# RoverWing-cover-V5.net
KiCad netlist of a schematic drawn in EAGLE
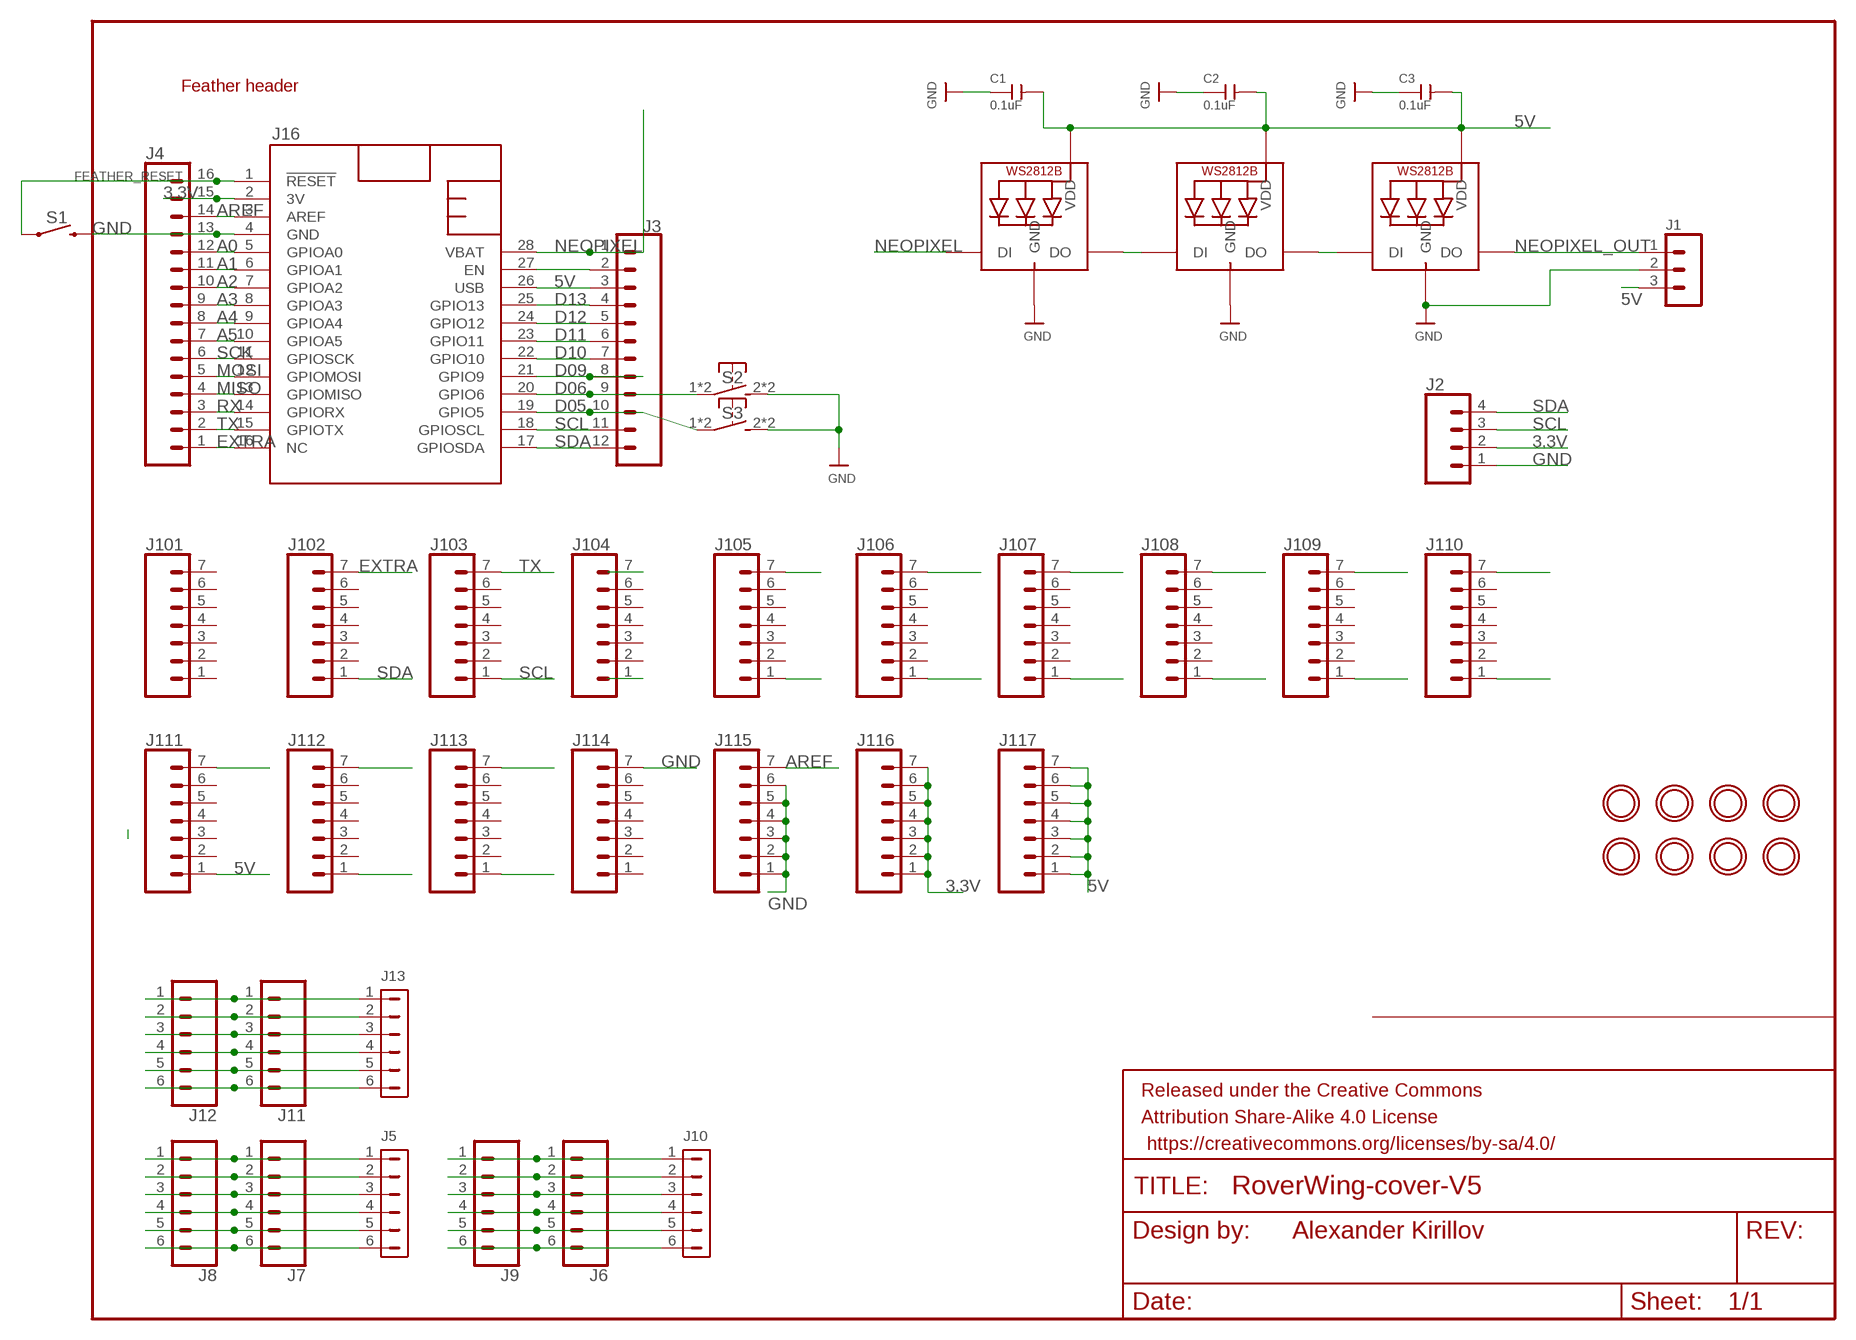
[diagram p0: schematic, sheet 1]

(export (version "E")
  (design (tool "Eeschema 10.0.6"))
  (components
    (comp (ref "C1")
      (value "0.1uF")
      (footprint "eagle-import:C0805")
      (libsource (lib "eagle-import") (part "CAP-CERAMIC-SMD-0805"))
    )
    (comp (ref "C2")
      (value "0.1uF")
      (footprint "eagle-import:C0805")
      (libsource (lib "eagle-import") (part "CAP-CERAMIC-SMD-0805"))
    )
    (comp (ref "C3")
      (value "0.1uF")
      (footprint "eagle-import:C0805")
      (libsource (lib "eagle-import") (part "CAP-CERAMIC-SMD-0805"))
    )
    (comp (ref "FRAME2")
      (value "FRAME-LETTERNO_PACKAGE")
      (footprint "eagle-import:DUMMY")
      (fields (field (name "DESIGNER") "Nobody"))
      (libsource (lib "eagle-import") (part "FRAME-LETTERNO_PACKAGE"))
    )
    (comp (ref "J1")
      (value "HEADER-PH-3PSIDEENTRY")
      (footprint "eagle-import:S3B-PH-K")
      (fields (field (name "PARTNO") "S3B-PH-K-S(LF)(SN)"))
      (libsource (lib "eagle-import") (part "HEADER-PH-3PSIDEENTRY"))
    )
    (comp (ref "J2")
      (value "CONN_04")
      (footprint "eagle-import:1X04")
      (libsource (lib "eagle-import") (part "CONN_04"))
    )
    (comp (ref "J3")
      (value "CONN_12NO_SILK")
      (footprint "eagle-import:1X12_NO_SILK")
      (libsource (lib "eagle-import") (part "CONN_12NO_SILK"))
    )
    (comp (ref "J4")
      (value "CONN_161X16_NO_SILK")
      (footprint "eagle-import:1X16_NO_SILK")
      (libsource (lib "eagle-import") (part "CONN_161X16_NO_SILK"))
    )
    (comp (ref "J5")
      (value "HEADER-PH-6PSIDEENTRY")
      (footprint "eagle-import:S6B-PH-K")
      (libsource (lib "eagle-import") (part "HEADER-PH-6PSIDEENTRY"))
    )
    (comp (ref "J6")
      (value "CONN_06NO_SILK_NO_POP")
      (footprint "eagle-import:1X06_NO_SILK")
      (libsource (lib "eagle-import") (part "CONN_06NO_SILK_NO_POP"))
    )
    (comp (ref "J7")
      (value "CONN_06NO_SILK_NO_POP")
      (footprint "eagle-import:1X06_NO_SILK")
      (libsource (lib "eagle-import") (part "CONN_06NO_SILK_NO_POP"))
    )
    (comp (ref "J8")
      (value "CONN_06NO_SILK_NO_POP")
      (footprint "eagle-import:1X06_NO_SILK")
      (libsource (lib "eagle-import") (part "CONN_06NO_SILK_NO_POP"))
    )
    (comp (ref "J9")
      (value "CONN_06NO_SILK_NO_POP")
      (footprint "eagle-import:1X06_NO_SILK")
      (libsource (lib "eagle-import") (part "CONN_06NO_SILK_NO_POP"))
    )
    (comp (ref "J10")
      (value "HEADER-PH-6PSIDEENTRY")
      (footprint "eagle-import:S6B-PH-K")
      (libsource (lib "eagle-import") (part "HEADER-PH-6PSIDEENTRY"))
    )
    (comp (ref "J11")
      (value "CONN_06NO_SILK_NO_POP")
      (footprint "eagle-import:1X06_NO_SILK")
      (libsource (lib "eagle-import") (part "CONN_06NO_SILK_NO_POP"))
    )
    (comp (ref "J12")
      (value "CONN_06NO_SILK_NO_POP")
      (footprint "eagle-import:1X06_NO_SILK")
      (libsource (lib "eagle-import") (part "CONN_06NO_SILK_NO_POP"))
    )
    (comp (ref "J13")
      (value "HEADER-PH-6PSIDEENTRY")
      (footprint "eagle-import:S6B-PH-K")
      (libsource (lib "eagle-import") (part "HEADER-PH-6PSIDEENTRY"))
    )
    (comp (ref "J16")
      (value "FEATHERWING_NODIM")
      (footprint "eagle-import:FEATHERWING_DIM")
      (libsource (lib "eagle-import") (part "FEATHERWING_NODIM"))
    )
    (comp (ref "J101")
      (value "CONN_07NO_SILK")
      (footprint "eagle-import:1X07_NO_SILK")
      (libsource (lib "eagle-import") (part "CONN_07NO_SILK"))
    )
    (comp (ref "J102")
      (value "CONN_07NO_SILK")
      (footprint "eagle-import:1X07_NO_SILK")
      (libsource (lib "eagle-import") (part "CONN_07NO_SILK"))
    )
    (comp (ref "J103")
      (value "CONN_07NO_SILK")
      (footprint "eagle-import:1X07_NO_SILK")
      (libsource (lib "eagle-import") (part "CONN_07NO_SILK"))
    )
    (comp (ref "J104")
      (value "CONN_07NO_SILK")
      (footprint "eagle-import:1X07_NO_SILK")
      (libsource (lib "eagle-import") (part "CONN_07NO_SILK"))
    )
    (comp (ref "J105")
      (value "CONN_07NO_SILK")
      (footprint "eagle-import:1X07_NO_SILK")
      (libsource (lib "eagle-import") (part "CONN_07NO_SILK"))
    )
    (comp (ref "J106")
      (value "CONN_07NO_SILK")
      (footprint "eagle-import:1X07_NO_SILK")
      (libsource (lib "eagle-import") (part "CONN_07NO_SILK"))
    )
    (comp (ref "J107")
      (value "CONN_07NO_SILK")
      (footprint "eagle-import:1X07_NO_SILK")
      (libsource (lib "eagle-import") (part "CONN_07NO_SILK"))
    )
    (comp (ref "J108")
      (value "CONN_07NO_SILK")
      (footprint "eagle-import:1X07_NO_SILK")
      (libsource (lib "eagle-import") (part "CONN_07NO_SILK"))
    )
    (comp (ref "J109")
      (value "CONN_07NO_SILK")
      (footprint "eagle-import:1X07_NO_SILK")
      (libsource (lib "eagle-import") (part "CONN_07NO_SILK"))
    )
    (comp (ref "J110")
      (value "CONN_07NO_SILK")
      (footprint "eagle-import:1X07_NO_SILK")
      (libsource (lib "eagle-import") (part "CONN_07NO_SILK"))
    )
    (comp (ref "J111")
      (value "CONN_07NO_SILK")
      (footprint "eagle-import:1X07_NO_SILK")
      (libsource (lib "eagle-import") (part "CONN_07NO_SILK"))
    )
    (comp (ref "J112")
      (value "CONN_07NO_SILK")
      (footprint "eagle-import:1X07_NO_SILK")
      (libsource (lib "eagle-import") (part "CONN_07NO_SILK"))
    )
    (comp (ref "J113")
      (value "CONN_07NO_SILK")
      (footprint "eagle-import:1X07_NO_SILK")
      (libsource (lib "eagle-import") (part "CONN_07NO_SILK"))
    )
    (comp (ref "J114")
      (value "CONN_07NO_SILK")
      (footprint "eagle-import:1X07_NO_SILK")
      (libsource (lib "eagle-import") (part "CONN_07NO_SILK"))
    )
    (comp (ref "J115")
      (value "CONN_07NO_SILK")
      (footprint "eagle-import:1X07_NO_SILK")
      (libsource (lib "eagle-import") (part "CONN_07NO_SILK"))
    )
    (comp (ref "J116")
      (value "CONN_07NO_SILK")
      (footprint "eagle-import:1X07_NO_SILK")
      (libsource (lib "eagle-import") (part "CONN_07NO_SILK"))
    )
    (comp (ref "J117")
      (value "CONN_07NO_SILK")
      (footprint "eagle-import:1X07_NO_SILK")
      (libsource (lib "eagle-import") (part "CONN_07NO_SILK"))
    )
    (comp (ref "LED1")
      (value "WS2812B5050")
      (footprint "eagle-import:WS2812B")
      (libsource (lib "eagle-import") (part "WS2812B5050"))
    )
    (comp (ref "LED2")
      (value "WS2812B5050")
      (footprint "eagle-import:WS2812B")
      (libsource (lib "eagle-import") (part "WS2812B5050"))
    )
    (comp (ref "LED3")
      (value "WS2812B5050")
      (footprint "eagle-import:WS2812B")
      (libsource (lib "eagle-import") (part "WS2812B5050"))
    )
    (comp (ref "S1")
      (value "MOMENTARY-SWITCH-SPST-PTH-6.0MM")
      (footprint "eagle-import:TACTILE_SWITCH_PTH_6.0MM")
      (libsource (lib "eagle-import") (part "MOMENTARY-SWITCH-SPST-PTH-6.0MM"))
    )
    (comp (ref "S2")
      (value "SW-TACTILE-4.5X4.5_SMD")
      (footprint "eagle-import:TL3305")
      (libsource (lib "eagle-import") (part "SW-TACTILE-4.5X4.5_SMD"))
    )
    (comp (ref "S3")
      (value "SW-TACTILE-4.5X4.5_SMD")
      (footprint "eagle-import:TL3305")
      (libsource (lib "eagle-import") (part "SW-TACTILE-4.5X4.5_SMD"))
    )
    (comp (ref "U$3")
      (value "MOUNTINGHOLE3.0_NPH")
      (footprint "eagle-import:MOUNTINGHOLE_3.0_NPH")
      (libsource (lib "eagle-import") (part "MOUNTINGHOLE3.0_NPH"))
    )
    (comp (ref "U$4")
      (value "MOUNTINGHOLE3.0_NPH")
      (footprint "eagle-import:MOUNTINGHOLE_3.0_NPH")
      (libsource (lib "eagle-import") (part "MOUNTINGHOLE3.0_NPH"))
    )
    (comp (ref "U$14")
      (value "MOUNTINGHOLE3.0_NPH")
      (footprint "eagle-import:MOUNTINGHOLE_3.0_NPH")
      (libsource (lib "eagle-import") (part "MOUNTINGHOLE3.0_NPH"))
    )
    (comp (ref "U$15")
      (value "MOUNTINGHOLE3.0_NPH")
      (footprint "eagle-import:MOUNTINGHOLE_3.0_NPH")
      (libsource (lib "eagle-import") (part "MOUNTINGHOLE3.0_NPH"))
    )
    (comp (ref "U$24")
      (value "MOUNTINGHOLE3.0_NPH")
      (footprint "eagle-import:MOUNTINGHOLE_3.0_NPH")
      (libsource (lib "eagle-import") (part "MOUNTINGHOLE3.0_NPH"))
    )
    (comp (ref "U$25")
      (value "MOUNTINGHOLE3.0_NPH")
      (footprint "eagle-import:MOUNTINGHOLE_3.0_NPH")
      (libsource (lib "eagle-import") (part "MOUNTINGHOLE3.0_NPH"))
    )
    (comp (ref "U$26")
      (value "MOUNTINGHOLE3.0_NPH")
      (footprint "eagle-import:MOUNTINGHOLE_3.0_NPH")
      (libsource (lib "eagle-import") (part "MOUNTINGHOLE3.0_NPH"))
    )
    (comp (ref "U$27")
      (value "MOUNTINGHOLE3.0_NPH")
      (footprint "eagle-import:MOUNTINGHOLE_3.0_NPH")
      (libsource (lib "eagle-import") (part "MOUNTINGHOLE3.0_NPH"))
    )
  )
  (nets
    (net (code "1") (name "/3.3V") (class "Default")
      (node (ref "J116") (pin "1") (pinfunction "1_1") (pintype "passive"))
      (node (ref "J116") (pin "2") (pinfunction "2_2") (pintype "passive"))
      (node (ref "J116") (pin "3") (pinfunction "3_3") (pintype "passive"))
      (node (ref "J116") (pin "4") (pinfunction "4_4") (pintype "passive"))
      (node (ref "J116") (pin "5") (pinfunction "5_5") (pintype "passive"))
      (node (ref "J116") (pin "6") (pinfunction "6_6") (pintype "passive"))
      (node (ref "J116") (pin "7") (pinfunction "7_7") (pintype "passive"))
      (node (ref "J16") (pin "2") (pinfunction "3V_2") (pintype "power_in"))
      (node (ref "J2") (pin "2") (pinfunction "2_2") (pintype "passive"))
      (node (ref "J4") (pin "15") (pinfunction "15_15") (pintype "passive"))
    )
    (net (code "2") (name "/5V") (class "Default")
      (node (ref "C1") (pin "2") (pinfunction "2_2") (pintype "passive"))
      (node (ref "C2") (pin "2") (pinfunction "2_2") (pintype "passive"))
      (node (ref "C3") (pin "2") (pinfunction "2_2") (pintype "passive"))
      (node (ref "J1") (pin "3") (pinfunction "3_3") (pintype "passive"))
      (node (ref "J111") (pin "1") (pinfunction "1_1") (pintype "passive"))
      (node (ref "J117") (pin "1") (pinfunction "1_1") (pintype "passive"))
      (node (ref "J117") (pin "2") (pinfunction "2_2") (pintype "passive"))
      (node (ref "J117") (pin "3") (pinfunction "3_3") (pintype "passive"))
      (node (ref "J117") (pin "4") (pinfunction "4_4") (pintype "passive"))
      (node (ref "J117") (pin "5") (pinfunction "5_5") (pintype "passive"))
      (node (ref "J117") (pin "6") (pinfunction "6_6") (pintype "passive"))
      (node (ref "J117") (pin "7") (pinfunction "7_7") (pintype "passive"))
      (node (ref "J16") (pin "26") (pinfunction "USB_26") (pintype "power_in"))
      (node (ref "J3") (pin "3") (pinfunction "3_3") (pintype "passive"))
      (node (ref "LED1") (pin "1-VDD") (pinfunction "VDD_1-VDD") (pintype "power_in"))
      (node (ref "LED2") (pin "1-VDD") (pinfunction "VDD_1-VDD") (pintype "power_in"))
      (node (ref "LED3") (pin "1-VDD") (pinfunction "VDD_1-VDD") (pintype "power_in"))
    )
    (net (code "3") (name "/A0") (class "Default")
      (node (ref "J113") (pin "7") (pinfunction "7_7") (pintype "passive"))
      (node (ref "J16") (pin "5") (pinfunction "GPIOA0_5") (pintype "bidirectional"))
      (node (ref "J4") (pin "12") (pinfunction "12_12") (pintype "passive"))
    )
    (net (code "4") (name "/A1") (class "Default")
      (node (ref "J112") (pin "7") (pinfunction "7_7") (pintype "passive"))
      (node (ref "J16") (pin "6") (pinfunction "GPIOA1_6") (pintype "bidirectional"))
      (node (ref "J4") (pin "11") (pinfunction "11_11") (pintype "passive"))
    )
    (net (code "5") (name "/A2") (class "Default")
      (node (ref "J111") (pin "7") (pinfunction "7_7") (pintype "passive"))
      (node (ref "J16") (pin "7") (pinfunction "GPIOA2_7") (pintype "bidirectional"))
      (node (ref "J4") (pin "10") (pinfunction "10_10") (pintype "passive"))
    )
    (net (code "6") (name "/A3") (class "Default")
      (node (ref "J110") (pin "7") (pinfunction "7_7") (pintype "passive"))
      (node (ref "J16") (pin "8") (pinfunction "GPIOA3_8") (pintype "bidirectional"))
      (node (ref "J4") (pin "9") (pinfunction "9_9") (pintype "passive"))
    )
    (net (code "7") (name "/A4") (class "Default")
      (node (ref "J109") (pin "7") (pinfunction "7_7") (pintype "passive"))
      (node (ref "J16") (pin "9") (pinfunction "GPIOA4_9") (pintype "bidirectional"))
      (node (ref "J4") (pin "8") (pinfunction "8_8") (pintype "passive"))
    )
    (net (code "8") (name "/A5") (class "Default")
      (node (ref "J108") (pin "7") (pinfunction "7_7") (pintype "passive"))
      (node (ref "J16") (pin "10") (pinfunction "GPIOA5_10") (pintype "bidirectional"))
      (node (ref "J4") (pin "7") (pinfunction "7_7") (pintype "passive"))
    )
    (net (code "9") (name "/AREF") (class "Default")
      (node (ref "J115") (pin "7") (pinfunction "7_7") (pintype "passive"))
      (node (ref "J16") (pin "3") (pinfunction "AREF_3") (pintype "passive"))
      (node (ref "J4") (pin "14") (pinfunction "14_14") (pintype "passive"))
    )
    (net (code "10") (name "/D05") (class "Default")
      (node (ref "J104") (pin "1") (pinfunction "1_1") (pintype "passive"))
      (node (ref "J16") (pin "19") (pinfunction "GPIO5_19") (pintype "bidirectional"))
      (node (ref "J3") (pin "10") (pinfunction "10_10") (pintype "passive"))
      (node (ref "S3") (pin "1") (pinfunction "P1_1") (pintype "passive"))
      (node (ref "S3") (pin "4") (pinfunction "P1_4") (pintype "passive"))
    )
    (net (code "11") (name "/D06") (class "Default")
      (node (ref "J105") (pin "1") (pinfunction "1_1") (pintype "passive"))
      (node (ref "J16") (pin "20") (pinfunction "GPIO6_20") (pintype "bidirectional"))
      (node (ref "J3") (pin "9") (pinfunction "9_9") (pintype "passive"))
      (node (ref "S2") (pin "1") (pinfunction "P1_1") (pintype "passive"))
      (node (ref "S2") (pin "4") (pinfunction "P1_4") (pintype "passive"))
    )
    (net (code "12") (name "/D09") (class "Default")
      (node (ref "J106") (pin "1") (pinfunction "1_1") (pintype "passive"))
      (node (ref "J16") (pin "21") (pinfunction "GPIO9_21") (pintype "bidirectional"))
      (node (ref "J3") (pin "8") (pinfunction "8_8") (pintype "passive"))
    )
    (net (code "13") (name "/D10") (class "Default")
      (node (ref "J107") (pin "1") (pinfunction "1_1") (pintype "passive"))
      (node (ref "J16") (pin "22") (pinfunction "GPIO10_22") (pintype "bidirectional"))
      (node (ref "J3") (pin "7") (pinfunction "7_7") (pintype "passive"))
    )
    (net (code "14") (name "/D11") (class "Default")
      (node (ref "J108") (pin "1") (pinfunction "1_1") (pintype "passive"))
      (node (ref "J16") (pin "23") (pinfunction "GPIO11_23") (pintype "bidirectional"))
      (node (ref "J3") (pin "6") (pinfunction "6_6") (pintype "passive"))
    )
    (net (code "15") (name "/D12") (class "Default")
      (node (ref "J109") (pin "1") (pinfunction "1_1") (pintype "passive"))
      (node (ref "J16") (pin "24") (pinfunction "GPIO12_24") (pintype "bidirectional"))
      (node (ref "J3") (pin "5") (pinfunction "5_5") (pintype "passive"))
    )
    (net (code "16") (name "/D13") (class "Default")
      (node (ref "J110") (pin "1") (pinfunction "1_1") (pintype "passive"))
      (node (ref "J16") (pin "25") (pinfunction "GPIO13_25") (pintype "bidirectional"))
      (node (ref "J3") (pin "4") (pinfunction "4_4") (pintype "passive"))
    )
    (net (code "17") (name "/EXTRA") (class "Default")
      (node (ref "J102") (pin "7") (pinfunction "7_7") (pintype "passive"))
      (node (ref "J16") (pin "16") (pinfunction "NC_16") (pintype "passive"))
      (node (ref "J4") (pin "1") (pinfunction "1_1") (pintype "passive"))
    )
    (net (code "18") (name "/FEATHER_RESET") (class "Default")
      (node (ref "J16") (pin "1") (pinfunction "~{RESET}_1") (pintype "input"))
      (node (ref "J4") (pin "16") (pinfunction "16_16") (pintype "passive"))
      (node (ref "S1") (pin "1") (pinfunction "1_1") (pintype "passive"))
    )
    (net (code "19") (name "/MISO") (class "Default")
      (node (ref "J105") (pin "7") (pinfunction "7_7") (pintype "passive"))
      (node (ref "J16") (pin "13") (pinfunction "GPIOMISO_13") (pintype "bidirectional"))
      (node (ref "J4") (pin "4") (pinfunction "4_4") (pintype "passive"))
    )
    (net (code "20") (name "/MOSI") (class "Default")
      (node (ref "J106") (pin "7") (pinfunction "7_7") (pintype "passive"))
      (node (ref "J16") (pin "12") (pinfunction "GPIOMOSI_12") (pintype "bidirectional"))
      (node (ref "J4") (pin "5") (pinfunction "5_5") (pintype "passive"))
    )
    (net (code "21") (name "/N$37") (class "Default")
      (node (ref "J112") (pin "1") (pinfunction "1_1") (pintype "passive"))
      (node (ref "J16") (pin "27") (pinfunction "EN_27") (pintype "passive"))
      (node (ref "J3") (pin "2") (pinfunction "2_2") (pintype "passive"))
    )
    (net (code "22") (name "/NEOPIXEL") (class "Default")
      (node (ref "J16") (pin "28") (pinfunction "VBAT_28") (pintype "power_in"))
      (node (ref "J3") (pin "1") (pinfunction "1_1") (pintype "passive"))
      (node (ref "LED1") (pin "4-DIN") (pinfunction "DI_4-DIN") (pintype "input"))
    )
    (net (code "23") (name "/NEOPIXEL_OUT") (class "Default")
      (node (ref "J1") (pin "1") (pinfunction "1_1") (pintype "passive"))
      (node (ref "LED3") (pin "2-DOUT") (pinfunction "DO_2-DOUT") (pintype "output"))
    )
    (net (code "24") (name "/RX") (class "Default")
      (node (ref "J104") (pin "7") (pinfunction "7_7") (pintype "passive"))
      (node (ref "J16") (pin "14") (pinfunction "GPIORX_14") (pintype "bidirectional"))
      (node (ref "J4") (pin "3") (pinfunction "3_3") (pintype "passive"))
    )
    (net (code "25") (name "/SCK") (class "Default")
      (node (ref "J107") (pin "7") (pinfunction "7_7") (pintype "passive"))
      (node (ref "J16") (pin "11") (pinfunction "GPIOSCK_11") (pintype "bidirectional"))
      (node (ref "J4") (pin "6") (pinfunction "6_6") (pintype "passive"))
    )
    (net (code "26") (name "/SCL") (class "Default")
      (node (ref "J103") (pin "1") (pinfunction "1_1") (pintype "passive"))
      (node (ref "J16") (pin "18") (pinfunction "GPIOSCL_18") (pintype "bidirectional"))
      (node (ref "J2") (pin "3") (pinfunction "3_3") (pintype "passive"))
      (node (ref "J3") (pin "11") (pinfunction "11_11") (pintype "passive"))
    )
    (net (code "27") (name "/SDA") (class "Default")
      (node (ref "J102") (pin "1") (pinfunction "1_1") (pintype "passive"))
      (node (ref "J16") (pin "17") (pinfunction "GPIOSDA_17") (pintype "bidirectional"))
      (node (ref "J2") (pin "4") (pinfunction "4_4") (pintype "passive"))
      (node (ref "J3") (pin "12") (pinfunction "12_12") (pintype "passive"))
    )
    (net (code "28") (name "/TX") (class "Default")
      (node (ref "J103") (pin "7") (pinfunction "7_7") (pintype "passive"))
      (node (ref "J16") (pin "15") (pinfunction "GPIOTX_15") (pintype "bidirectional"))
      (node (ref "J4") (pin "2") (pinfunction "2_2") (pintype "passive"))
    )
    (net (code "29") (name "GND") (class "Default")
      (node (ref "C1") (pin "1") (pinfunction "1_1") (pintype "passive"))
      (node (ref "C2") (pin "1") (pinfunction "1_1") (pintype "passive"))
      (node (ref "C3") (pin "1") (pinfunction "1_1") (pintype "passive"))
      (node (ref "J1") (pin "2") (pinfunction "2_2") (pintype "passive"))
      (node (ref "J114") (pin "7") (pinfunction "7_7") (pintype "passive"))
      (node (ref "J115") (pin "1") (pinfunction "1_1") (pintype "passive"))
      (node (ref "J115") (pin "2") (pinfunction "2_2") (pintype "passive"))
      (node (ref "J115") (pin "3") (pinfunction "3_3") (pintype "passive"))
      (node (ref "J115") (pin "4") (pinfunction "4_4") (pintype "passive"))
      (node (ref "J115") (pin "5") (pinfunction "5_5") (pintype "passive"))
      (node (ref "J115") (pin "6") (pinfunction "6_6") (pintype "passive"))
      (node (ref "J16") (pin "4") (pinfunction "GND_4") (pintype "power_in"))
      (node (ref "J2") (pin "1") (pinfunction "1_1") (pintype "passive"))
      (node (ref "J4") (pin "13") (pinfunction "13_13") (pintype "passive"))
      (node (ref "LED1") (pin "3-GND") (pinfunction "GND_3-GND") (pintype "power_in"))
      (node (ref "LED2") (pin "3-GND") (pinfunction "GND_3-GND") (pintype "power_in"))
      (node (ref "LED3") (pin "3-GND") (pinfunction "GND_3-GND") (pintype "power_in"))
      (node (ref "S1") (pin "3") (pinfunction "2_3") (pintype "passive"))
      (node (ref "S2") (pin "2") (pinfunction "S1_2") (pintype "passive"))
      (node (ref "S2") (pin "3") (pinfunction "S1_3") (pintype "passive"))
      (node (ref "S3") (pin "2") (pinfunction "S1_2") (pintype "passive"))
      (node (ref "S3") (pin "3") (pinfunction "S1_3") (pintype "passive"))
    )
    (net (code "30") (name "Net-(J5-Pad1)") (class "Default")
      (node (ref "J5") (pin "1") (pinfunction "1_1") (pintype "passive"))
      (node (ref "J7") (pin "1") (pinfunction "1_1") (pintype "passive"))
      (node (ref "J8") (pin "1") (pinfunction "1_1") (pintype "passive"))
    )
    (net (code "31") (name "Net-(J5-Pad2)") (class "Default")
      (node (ref "J5") (pin "2") (pinfunction "2_2") (pintype "passive"))
      (node (ref "J7") (pin "2") (pinfunction "2_2") (pintype "passive"))
      (node (ref "J8") (pin "2") (pinfunction "2_2") (pintype "passive"))
    )
    (net (code "32") (name "Net-(J5-Pad3)") (class "Default")
      (node (ref "J5") (pin "3") (pinfunction "3_3") (pintype "passive"))
      (node (ref "J7") (pin "3") (pinfunction "3_3") (pintype "passive"))
      (node (ref "J8") (pin "3") (pinfunction "3_3") (pintype "passive"))
    )
    (net (code "33") (name "Net-(J5-Pad4)") (class "Default")
      (node (ref "J5") (pin "4") (pinfunction "4_4") (pintype "passive"))
      (node (ref "J7") (pin "4") (pinfunction "4_4") (pintype "passive"))
      (node (ref "J8") (pin "4") (pinfunction "4_4") (pintype "passive"))
    )
    (net (code "34") (name "Net-(J5-Pad5)") (class "Default")
      (node (ref "J5") (pin "5") (pinfunction "5_5") (pintype "passive"))
      (node (ref "J7") (pin "5") (pinfunction "5_5") (pintype "passive"))
      (node (ref "J8") (pin "5") (pinfunction "5_5") (pintype "passive"))
    )
    (net (code "35") (name "Net-(J5-Pad6)") (class "Default")
      (node (ref "J5") (pin "6") (pinfunction "6_6") (pintype "passive"))
      (node (ref "J7") (pin "6") (pinfunction "6_6") (pintype "passive"))
      (node (ref "J8") (pin "6") (pinfunction "6_6") (pintype "passive"))
    )
    (net (code "36") (name "Net-(J10-Pad1)") (class "Default")
      (node (ref "J10") (pin "1") (pinfunction "1_1") (pintype "passive"))
      (node (ref "J6") (pin "1") (pinfunction "1_1") (pintype "passive"))
      (node (ref "J9") (pin "1") (pinfunction "1_1") (pintype "passive"))
    )
    (net (code "37") (name "Net-(J10-Pad2)") (class "Default")
      (node (ref "J10") (pin "2") (pinfunction "2_2") (pintype "passive"))
      (node (ref "J6") (pin "2") (pinfunction "2_2") (pintype "passive"))
      (node (ref "J9") (pin "2") (pinfunction "2_2") (pintype "passive"))
    )
    (net (code "38") (name "Net-(J10-Pad3)") (class "Default")
      (node (ref "J10") (pin "3") (pinfunction "3_3") (pintype "passive"))
      (node (ref "J6") (pin "3") (pinfunction "3_3") (pintype "passive"))
      (node (ref "J9") (pin "3") (pinfunction "3_3") (pintype "passive"))
    )
    (net (code "39") (name "Net-(J10-Pad4)") (class "Default")
      (node (ref "J10") (pin "4") (pinfunction "4_4") (pintype "passive"))
      (node (ref "J6") (pin "4") (pinfunction "4_4") (pintype "passive"))
      (node (ref "J9") (pin "4") (pinfunction "4_4") (pintype "passive"))
    )
    (net (code "40") (name "Net-(J10-Pad5)") (class "Default")
      (node (ref "J10") (pin "5") (pinfunction "5_5") (pintype "passive"))
      (node (ref "J6") (pin "5") (pinfunction "5_5") (pintype "passive"))
      (node (ref "J9") (pin "5") (pinfunction "5_5") (pintype "passive"))
    )
    (net (code "41") (name "Net-(J10-Pad6)") (class "Default")
      (node (ref "J10") (pin "6") (pinfunction "6_6") (pintype "passive"))
      (node (ref "J6") (pin "6") (pinfunction "6_6") (pintype "passive"))
      (node (ref "J9") (pin "6") (pinfunction "6_6") (pintype "passive"))
    )
    (net (code "42") (name "Net-(J11-Pad1)") (class "Default")
      (node (ref "J11") (pin "1") (pinfunction "1_1") (pintype "passive"))
      (node (ref "J12") (pin "1") (pinfunction "1_1") (pintype "passive"))
      (node (ref "J13") (pin "1") (pinfunction "1_1") (pintype "passive"))
    )
    (net (code "43") (name "Net-(J11-Pad2)") (class "Default")
      (node (ref "J11") (pin "2") (pinfunction "2_2") (pintype "passive"))
      (node (ref "J12") (pin "2") (pinfunction "2_2") (pintype "passive"))
      (node (ref "J13") (pin "2") (pinfunction "2_2") (pintype "passive"))
    )
    (net (code "44") (name "Net-(J11-Pad3)") (class "Default")
      (node (ref "J11") (pin "3") (pinfunction "3_3") (pintype "passive"))
      (node (ref "J12") (pin "3") (pinfunction "3_3") (pintype "passive"))
      (node (ref "J13") (pin "3") (pinfunction "3_3") (pintype "passive"))
    )
    (net (code "45") (name "Net-(J11-Pad4)") (class "Default")
      (node (ref "J11") (pin "4") (pinfunction "4_4") (pintype "passive"))
      (node (ref "J12") (pin "4") (pinfunction "4_4") (pintype "passive"))
      (node (ref "J13") (pin "4") (pinfunction "4_4") (pintype "passive"))
    )
    (net (code "46") (name "Net-(J11-Pad5)") (class "Default")
      (node (ref "J11") (pin "5") (pinfunction "5_5") (pintype "passive"))
      (node (ref "J12") (pin "5") (pinfunction "5_5") (pintype "passive"))
      (node (ref "J13") (pin "5") (pinfunction "5_5") (pintype "passive"))
    )
    (net (code "47") (name "Net-(J11-Pad6)") (class "Default")
      (node (ref "J11") (pin "6") (pinfunction "6_6") (pintype "passive"))
      (node (ref "J12") (pin "6") (pinfunction "6_6") (pintype "passive"))
      (node (ref "J13") (pin "6") (pinfunction "6_6") (pintype "passive"))
    )
    (net (code "48") (name "Net-(LED1-DO)") (class "Default")
      (node (ref "LED1") (pin "2-DOUT") (pinfunction "DO_2-DOUT") (pintype "output"))
      (node (ref "LED2") (pin "4-DIN") (pinfunction "DI_4-DIN") (pintype "input"))
    )
    (net (code "49") (name "Net-(LED2-DO)") (class "Default")
      (node (ref "LED2") (pin "2-DOUT") (pinfunction "DO_2-DOUT") (pintype "output"))
      (node (ref "LED3") (pin "4-DIN") (pinfunction "DI_4-DIN") (pintype "input"))
    )
    (net (code "50") (name "unconnected-(J101-Pad1)") (class "Default")
      (node (ref "J101") (pin "1") (pinfunction "1_1") (pintype "passive"))
    )
    (net (code "51") (name "unconnected-(J101-Pad2)") (class "Default")
      (node (ref "J101") (pin "2") (pinfunction "2_2") (pintype "passive"))
    )
    (net (code "52") (name "unconnected-(J101-Pad3)") (class "Default")
      (node (ref "J101") (pin "3") (pinfunction "3_3") (pintype "passive"))
    )
    (net (code "53") (name "unconnected-(J101-Pad4)") (class "Default")
      (node (ref "J101") (pin "4") (pinfunction "4_4") (pintype "passive"))
    )
    (net (code "54") (name "unconnected-(J101-Pad5)") (class "Default")
      (node (ref "J101") (pin "5") (pinfunction "5_5") (pintype "passive"))
    )
    (net (code "55") (name "unconnected-(J101-Pad6)") (class "Default")
      (node (ref "J101") (pin "6") (pinfunction "6_6") (pintype "passive"))
    )
    (net (code "56") (name "unconnected-(J101-Pad7)") (class "Default")
      (node (ref "J101") (pin "7") (pinfunction "7_7") (pintype "passive"))
    )
    (net (code "57") (name "unconnected-(J102-Pad2)") (class "Default")
      (node (ref "J102") (pin "2") (pinfunction "2_2") (pintype "passive"))
    )
    (net (code "58") (name "unconnected-(J102-Pad3)") (class "Default")
      (node (ref "J102") (pin "3") (pinfunction "3_3") (pintype "passive"))
    )
    (net (code "59") (name "unconnected-(J102-Pad4)") (class "Default")
      (node (ref "J102") (pin "4") (pinfunction "4_4") (pintype "passive"))
    )
    (net (code "60") (name "unconnected-(J102-Pad5)") (class "Default")
      (node (ref "J102") (pin "5") (pinfunction "5_5") (pintype "passive"))
    )
    (net (code "61") (name "unconnected-(J102-Pad6)") (class "Default")
      (node (ref "J102") (pin "6") (pinfunction "6_6") (pintype "passive"))
    )
    (net (code "62") (name "unconnected-(J103-Pad2)") (class "Default")
      (node (ref "J103") (pin "2") (pinfunction "2_2") (pintype "passive"))
    )
    (net (code "63") (name "unconnected-(J103-Pad3)") (class "Default")
      (node (ref "J103") (pin "3") (pinfunction "3_3") (pintype "passive"))
    )
    (net (code "64") (name "unconnected-(J103-Pad4)") (class "Default")
      (node (ref "J103") (pin "4") (pinfunction "4_4") (pintype "passive"))
    )
    (net (code "65") (name "unconnected-(J103-Pad5)") (class "Default")
      (node (ref "J103") (pin "5") (pinfunction "5_5") (pintype "passive"))
    )
    (net (code "66") (name "unconnected-(J103-Pad6)") (class "Default")
      (node (ref "J103") (pin "6") (pinfunction "6_6") (pintype "passive"))
    )
    (net (code "67") (name "unconnected-(J104-Pad2)") (class "Default")
      (node (ref "J104") (pin "2") (pinfunction "2_2") (pintype "passive"))
    )
    (net (code "68") (name "unconnected-(J104-Pad3)") (class "Default")
      (node (ref "J104") (pin "3") (pinfunction "3_3") (pintype "passive"))
    )
    (net (code "69") (name "unconnected-(J104-Pad4)") (class "Default")
      (node (ref "J104") (pin "4") (pinfunction "4_4") (pintype "passive"))
    )
    (net (code "70") (name "unconnected-(J104-Pad5)") (class "Default")
      (node (ref "J104") (pin "5") (pinfunction "5_5") (pintype "passive"))
    )
    (net (code "71") (name "unconnected-(J104-Pad6)") (class "Default")
      (node (ref "J104") (pin "6") (pinfunction "6_6") (pintype "passive"))
    )
    (net (code "72") (name "unconnected-(J105-Pad2)") (class "Default")
      (node (ref "J105") (pin "2") (pinfunction "2_2") (pintype "passive"))
    )
    (net (code "73") (name "unconnected-(J105-Pad3)") (class "Default")
      (node (ref "J105") (pin "3") (pinfunction "3_3") (pintype "passive"))
    )
    (net (code "74") (name "unconnected-(J105-Pad4)") (class "Default")
      (node (ref "J105") (pin "4") (pinfunction "4_4") (pintype "passive"))
    )
    (net (code "75") (name "unconnected-(J105-Pad5)") (class "Default")
      (node (ref "J105") (pin "5") (pinfunction "5_5") (pintype "passive"))
    )
    (net (code "76") (name "unconnected-(J105-Pad6)") (class "Default")
      (node (ref "J105") (pin "6") (pinfunction "6_6") (pintype "passive"))
    )
    (net (code "77") (name "unconnected-(J106-Pad2)") (class "Default")
      (node (ref "J106") (pin "2") (pinfunction "2_2") (pintype "passive"))
    )
    (net (code "78") (name "unconnected-(J106-Pad3)") (class "Default")
      (node (ref "J106") (pin "3") (pinfunction "3_3") (pintype "passive"))
    )
    (net (code "79") (name "unconnected-(J106-Pad4)") (class "Default")
      (node (ref "J106") (pin "4") (pinfunction "4_4") (pintype "passive"))
    )
    (net (code "80") (name "unconnected-(J106-Pad5)") (class "Default")
      (node (ref "J106") (pin "5") (pinfunction "5_5") (pintype "passive"))
    )
    (net (code "81") (name "unconnected-(J106-Pad6)") (class "Default")
      (node (ref "J106") (pin "6") (pinfunction "6_6") (pintype "passive"))
    )
    (net (code "82") (name "unconnected-(J107-Pad2)") (class "Default")
      (node (ref "J107") (pin "2") (pinfunction "2_2") (pintype "passive"))
    )
    (net (code "83") (name "unconnected-(J107-Pad3)") (class "Default")
      (node (ref "J107") (pin "3") (pinfunction "3_3") (pintype "passive"))
    )
    (net (code "84") (name "unconnected-(J107-Pad4)") (class "Default")
      (node (ref "J107") (pin "4") (pinfunction "4_4") (pintype "passive"))
    )
    (net (code "85") (name "unconnected-(J107-Pad5)") (class "Default")
      (node (ref "J107") (pin "5") (pinfunction "5_5") (pintype "passive"))
    )
    (net (code "86") (name "unconnected-(J107-Pad6)") (class "Default")
      (node (ref "J107") (pin "6") (pinfunction "6_6") (pintype "passive"))
    )
    (net (code "87") (name "unconnected-(J108-Pad2)") (class "Default")
      (node (ref "J108") (pin "2") (pinfunction "2_2") (pintype "passive"))
    )
    (net (code "88") (name "unconnected-(J108-Pad3)") (class "Default")
      (node (ref "J108") (pin "3") (pinfunction "3_3") (pintype "passive"))
    )
    (net (code "89") (name "unconnected-(J108-Pad4)") (class "Default")
      (node (ref "J108") (pin "4") (pinfunction "4_4") (pintype "passive"))
    )
    (net (code "90") (name "unconnected-(J108-Pad5)") (class "Default")
      (node (ref "J108") (pin "5") (pinfunction "5_5") (pintype "passive"))
    )
    (net (code "91") (name "unconnected-(J108-Pad6)") (class "Default")
      (node (ref "J108") (pin "6") (pinfunction "6_6") (pintype "passive"))
    )
    (net (code "92") (name "unconnected-(J109-Pad2)") (class "Default")
      (node (ref "J109") (pin "2") (pinfunction "2_2") (pintype "passive"))
    )
    (net (code "93") (name "unconnected-(J109-Pad3)") (class "Default")
      (node (ref "J109") (pin "3") (pinfunction "3_3") (pintype "passive"))
    )
    (net (code "94") (name "unconnected-(J109-Pad4)") (class "Default")
      (node (ref "J109") (pin "4") (pinfunction "4_4") (pintype "passive"))
    )
    (net (code "95") (name "unconnected-(J109-Pad5)") (class "Default")
      (node (ref "J109") (pin "5") (pinfunction "5_5") (pintype "passive"))
    )
    (net (code "96") (name "unconnected-(J109-Pad6)") (class "Default")
      (node (ref "J109") (pin "6") (pinfunction "6_6") (pintype "passive"))
    )
    (net (code "97") (name "unconnected-(J110-Pad2)") (class "Default")
      (node (ref "J110") (pin "2") (pinfunction "2_2") (pintype "passive"))
    )
    (net (code "98") (name "unconnected-(J110-Pad3)") (class "Default")
      (node (ref "J110") (pin "3") (pinfunction "3_3") (pintype "passive"))
    )
    (net (code "99") (name "unconnected-(J110-Pad4)") (class "Default")
      (node (ref "J110") (pin "4") (pinfunction "4_4") (pintype "passive"))
    )
    (net (code "100") (name "unconnected-(J110-Pad5)") (class "Default")
      (node (ref "J110") (pin "5") (pinfunction "5_5") (pintype "passive"))
    )
    (net (code "101") (name "unconnected-(J110-Pad6)") (class "Default")
      (node (ref "J110") (pin "6") (pinfunction "6_6") (pintype "passive"))
    )
    (net (code "102") (name "unconnected-(J111-Pad2)") (class "Default")
      (node (ref "J111") (pin "2") (pinfunction "2_2") (pintype "passive"))
    )
    (net (code "103") (name "unconnected-(J111-Pad3)") (class "Default")
      (node (ref "J111") (pin "3") (pinfunction "3_3") (pintype "passive"))
    )
    (net (code "104") (name "unconnected-(J111-Pad4)") (class "Default")
      (node (ref "J111") (pin "4") (pinfunction "4_4") (pintype "passive"))
    )
    (net (code "105") (name "unconnected-(J111-Pad5)") (class "Default")
      (node (ref "J111") (pin "5") (pinfunction "5_5") (pintype "passive"))
    )
    (net (code "106") (name "unconnected-(J111-Pad6)") (class "Default")
      (node (ref "J111") (pin "6") (pinfunction "6_6") (pintype "passive"))
    )
    (net (code "107") (name "unconnected-(J112-Pad2)") (class "Default")
      (node (ref "J112") (pin "2") (pinfunction "2_2") (pintype "passive"))
    )
    (net (code "108") (name "unconnected-(J112-Pad3)") (class "Default")
      (node (ref "J112") (pin "3") (pinfunction "3_3") (pintype "passive"))
    )
    (net (code "109") (name "unconnected-(J112-Pad4)") (class "Default")
      (node (ref "J112") (pin "4") (pinfunction "4_4") (pintype "passive"))
    )
    (net (code "110") (name "unconnected-(J112-Pad5)") (class "Default")
      (node (ref "J112") (pin "5") (pinfunction "5_5") (pintype "passive"))
    )
    (net (code "111") (name "unconnected-(J112-Pad6)") (class "Default")
      (node (ref "J112") (pin "6") (pinfunction "6_6") (pintype "passive"))
    )
    (net (code "112") (name "unconnected-(J113-Pad1)") (class "Default")
      (node (ref "J113") (pin "1") (pinfunction "1_1") (pintype "passive"))
    )
    (net (code "113") (name "unconnected-(J113-Pad2)") (class "Default")
      (node (ref "J113") (pin "2") (pinfunction "2_2") (pintype "passive"))
    )
    (net (code "114") (name "unconnected-(J113-Pad3)") (class "Default")
      (node (ref "J113") (pin "3") (pinfunction "3_3") (pintype "passive"))
    )
    (net (code "115") (name "unconnected-(J113-Pad4)") (class "Default")
      (node (ref "J113") (pin "4") (pinfunction "4_4") (pintype "passive"))
    )
    (net (code "116") (name "unconnected-(J113-Pad5)") (class "Default")
      (node (ref "J113") (pin "5") (pinfunction "5_5") (pintype "passive"))
    )
    (net (code "117") (name "unconnected-(J113-Pad6)") (class "Default")
      (node (ref "J113") (pin "6") (pinfunction "6_6") (pintype "passive"))
    )
    (net (code "118") (name "unconnected-(J114-Pad1)") (class "Default")
      (node (ref "J114") (pin "1") (pinfunction "1_1") (pintype "passive"))
    )
    (net (code "119") (name "unconnected-(J114-Pad2)") (class "Default")
      (node (ref "J114") (pin "2") (pinfunction "2_2") (pintype "passive"))
    )
    (net (code "120") (name "unconnected-(J114-Pad3)") (class "Default")
      (node (ref "J114") (pin "3") (pinfunction "3_3") (pintype "passive"))
    )
    (net (code "121") (name "unconnected-(J114-Pad4)") (class "Default")
      (node (ref "J114") (pin "4") (pinfunction "4_4") (pintype "passive"))
    )
    (net (code "122") (name "unconnected-(J114-Pad5)") (class "Default")
      (node (ref "J114") (pin "5") (pinfunction "5_5") (pintype "passive"))
    )
    (net (code "123") (name "unconnected-(J114-Pad6)") (class "Default")
      (node (ref "J114") (pin "6") (pinfunction "6_6") (pintype "passive"))
    )
  )
)
